# 02_LEDs.net
KiCad netlist of a schematic drawn in Altium Designer
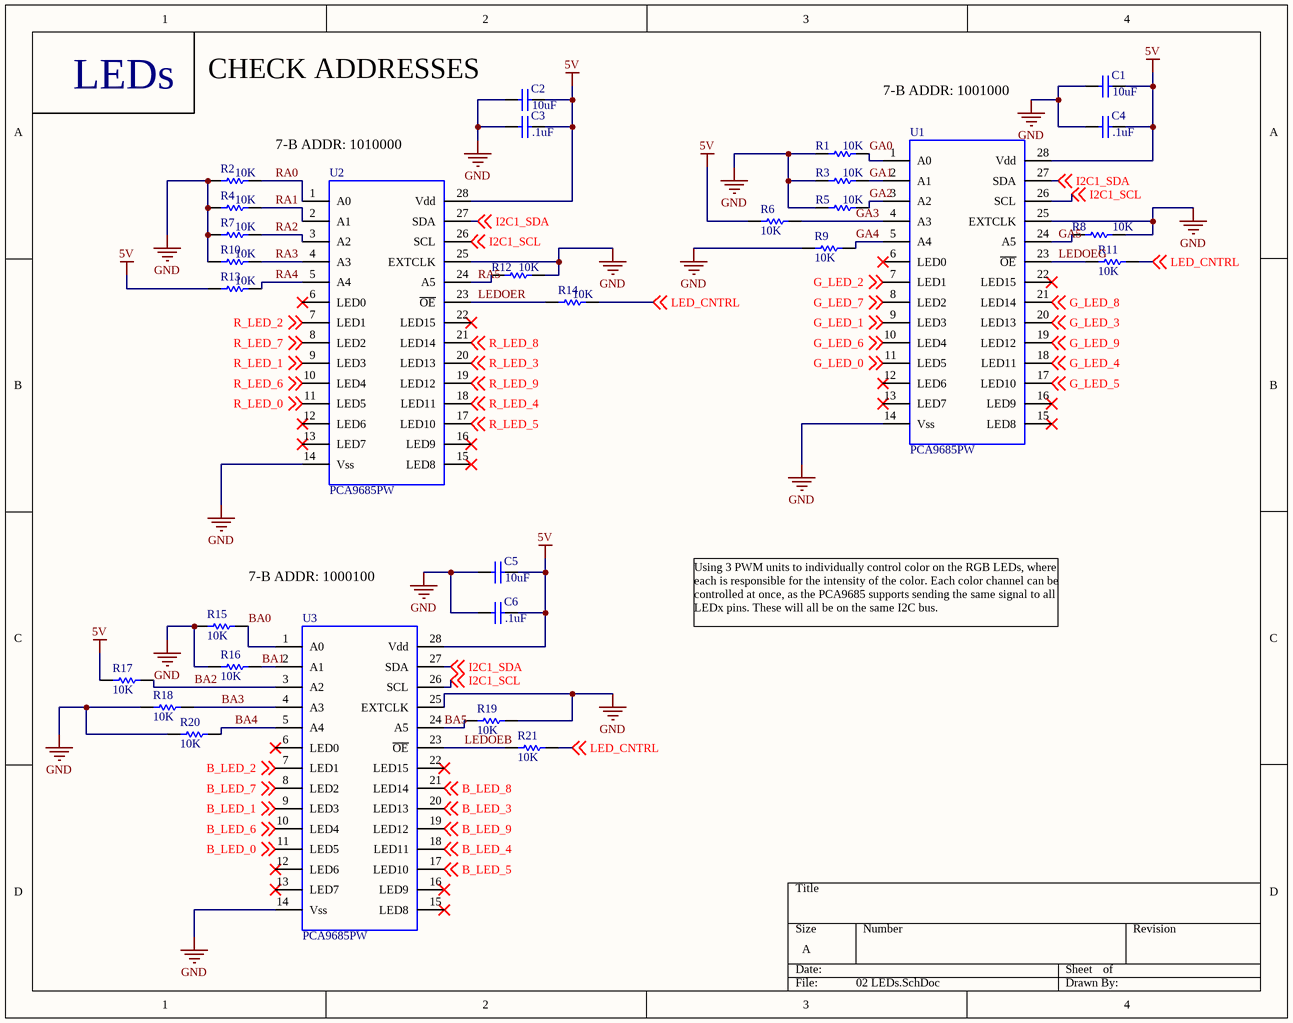
[diagram p0: 02 LEDs.SchDoc]

(export (version "E")
  (design (tool "Eeschema 10.0.6"))
  (components
    (comp (ref "C1")
      (value "10uF")
      (footprint "CAPC2012X135N")
      (description "Cap Ceramic 10uF 16V X5R 10% SMD 0805 85C T/R")
      (fields
        (field (name "MANUFACTURER") "Johanson Dielectrics")
        (field (name "MANUFACTURER PART NUMBER") "160R15X106KV4E")
      )
      (libsource (lib "schlib_truman") (part "CAP_0805_10u_16V"))
    )
    (comp (ref "C2")
      (value "10uF")
      (footprint "CAPC2012X135N")
      (description "Cap Ceramic 10uF 16V X5R 10% SMD 0805 85C T/R")
      (fields
        (field (name "MANUFACTURER") "Johanson Dielectrics")
        (field (name "MANUFACTURER PART NUMBER") "160R15X106KV4E")
      )
      (libsource (lib "schlib_truman") (part "CAP_0805_10u_16V"))
    )
    (comp (ref "C3")
      (value ".1uF")
      (footprint "CAPC2012X135N")
      (description "Cap Ceramic 0.1uF 250V X7T 10% SMD 0805 125C Plastic T/R")
      (fields
        (field (name "MANUFACTURER") "TDK")
        (field (name "MANUFACTURER PART NUMBER") "C2012X7T2E104K125AE")
      )
      (libsource (lib "schlib_truman") (part "CAP_0805_.1u_250V"))
    )
    (comp (ref "C4")
      (value ".1uF")
      (footprint "CAPC2012X135N")
      (description "Cap Ceramic 0.1uF 250V X7T 10% SMD 0805 125C Plastic T/R")
      (fields
        (field (name "MANUFACTURER") "TDK")
        (field (name "MANUFACTURER PART NUMBER") "C2012X7T2E104K125AE")
      )
      (libsource (lib "schlib_truman") (part "CAP_0805_.1u_250V"))
    )
    (comp (ref "C5")
      (value "10uF")
      (footprint "CAPC2012X135N")
      (description "Cap Ceramic 10uF 16V X5R 10% SMD 0805 85C T/R")
      (fields
        (field (name "MANUFACTURER") "Johanson Dielectrics")
        (field (name "MANUFACTURER PART NUMBER") "160R15X106KV4E")
      )
      (libsource (lib "schlib_truman") (part "CAP_0805_10u_16V"))
    )
    (comp (ref "C6")
      (value ".1uF")
      (footprint "CAPC2012X135N")
      (description "Cap Ceramic 0.1uF 250V X7T 10% SMD 0805 125C Plastic T/R")
      (fields
        (field (name "MANUFACTURER") "TDK")
        (field (name "MANUFACTURER PART NUMBER") "C2012X7T2E104K125AE")
      )
      (libsource (lib "schlib_truman") (part "CAP_0805_.1u_250V"))
    )
    (comp (ref "R1")
      (value "RES_0805_10K")
      (footprint "RES0805")
      (description "RES, THICK FILM, 10K, 5%, 0.125W, 0805")
      (fields
        (field (name "MANUFACTURER") "Yageo")
        (field (name "MANUFACTURER PART NUMBER") "RC0805JR-0710KL")
        (field (name "RESISTANCE") "10K")
      )
      (libsource (lib "schlib_truman") (part "RES_0805_10K"))
    )
    (comp (ref "R2")
      (value "RES_0805_10K")
      (footprint "RES0805")
      (description "RES, THICK FILM, 10K, 5%, 0.125W, 0805")
      (fields
        (field (name "MANUFACTURER") "Yageo")
        (field (name "MANUFACTURER PART NUMBER") "RC0805JR-0710KL")
        (field (name "RESISTANCE") "10K")
      )
      (libsource (lib "schlib_truman") (part "RES_0805_10K"))
    )
    (comp (ref "R3")
      (value "RES_0805_10K")
      (footprint "RES0805")
      (description "RES, THICK FILM, 10K, 5%, 0.125W, 0805")
      (fields
        (field (name "MANUFACTURER") "Yageo")
        (field (name "MANUFACTURER PART NUMBER") "RC0805JR-0710KL")
        (field (name "RESISTANCE") "10K")
      )
      (libsource (lib "schlib_truman") (part "RES_0805_10K"))
    )
    (comp (ref "R4")
      (value "RES_0805_10K")
      (footprint "RES0805")
      (description "RES, THICK FILM, 10K, 5%, 0.125W, 0805")
      (fields
        (field (name "MANUFACTURER") "Yageo")
        (field (name "MANUFACTURER PART NUMBER") "RC0805JR-0710KL")
        (field (name "RESISTANCE") "10K")
      )
      (libsource (lib "schlib_truman") (part "RES_0805_10K"))
    )
    (comp (ref "R5")
      (value "RES_0805_10K")
      (footprint "RES0805")
      (description "RES, THICK FILM, 10K, 5%, 0.125W, 0805")
      (fields
        (field (name "MANUFACTURER") "Yageo")
        (field (name "MANUFACTURER PART NUMBER") "RC0805JR-0710KL")
        (field (name "RESISTANCE") "10K")
      )
      (libsource (lib "schlib_truman") (part "RES_0805_10K"))
    )
    (comp (ref "R6")
      (value "RES_0805_10K")
      (footprint "RES0805")
      (description "RES, THICK FILM, 10K, 5%, 0.125W, 0805")
      (fields
        (field (name "MANUFACTURER") "Yageo")
        (field (name "MANUFACTURER PART NUMBER") "RC0805JR-0710KL")
        (field (name "RESISTANCE") "10K")
      )
      (libsource (lib "schlib_truman") (part "RES_0805_10K"))
    )
    (comp (ref "R7")
      (value "RES_0805_10K")
      (footprint "RES0805")
      (description "RES, THICK FILM, 10K, 5%, 0.125W, 0805")
      (fields
        (field (name "MANUFACTURER") "Yageo")
        (field (name "MANUFACTURER PART NUMBER") "RC0805JR-0710KL")
        (field (name "RESISTANCE") "10K")
      )
      (libsource (lib "schlib_truman") (part "RES_0805_10K"))
    )
    (comp (ref "R8")
      (value "RES_0805_10K")
      (footprint "RES0805")
      (description "RES, THICK FILM, 10K, 5%, 0.125W, 0805")
      (fields
        (field (name "MANUFACTURER") "Yageo")
        (field (name "MANUFACTURER PART NUMBER") "RC0805JR-0710KL")
        (field (name "RESISTANCE") "10K")
      )
      (libsource (lib "schlib_truman") (part "RES_0805_10K"))
    )
    (comp (ref "R9")
      (value "RES_0805_10K")
      (footprint "RES0805")
      (description "RES, THICK FILM, 10K, 5%, 0.125W, 0805")
      (fields
        (field (name "MANUFACTURER") "Yageo")
        (field (name "MANUFACTURER PART NUMBER") "RC0805JR-0710KL")
        (field (name "RESISTANCE") "10K")
      )
      (libsource (lib "schlib_truman") (part "RES_0805_10K"))
    )
    (comp (ref "R10")
      (value "RES_0805_10K")
      (footprint "RES0805")
      (description "RES, THICK FILM, 10K, 5%, 0.125W, 0805")
      (fields
        (field (name "MANUFACTURER") "Yageo")
        (field (name "MANUFACTURER PART NUMBER") "RC0805JR-0710KL")
        (field (name "RESISTANCE") "10K")
      )
      (libsource (lib "schlib_truman") (part "RES_0805_10K"))
    )
    (comp (ref "R11")
      (value "RES_0805_10K")
      (footprint "RES0805")
      (description "RES, THICK FILM, 10K, 5%, 0.125W, 0805")
      (fields
        (field (name "MANUFACTURER") "Yageo")
        (field (name "MANUFACTURER PART NUMBER") "RC0805JR-0710KL")
        (field (name "RESISTANCE") "10K")
      )
      (libsource (lib "schlib_truman") (part "RES_0805_10K"))
    )
    (comp (ref "R12")
      (value "RES_0805_10K")
      (footprint "RES0805")
      (description "RES, THICK FILM, 10K, 5%, 0.125W, 0805")
      (fields
        (field (name "MANUFACTURER") "Yageo")
        (field (name "MANUFACTURER PART NUMBER") "RC0805JR-0710KL")
        (field (name "RESISTANCE") "10K")
      )
      (libsource (lib "schlib_truman") (part "RES_0805_10K"))
    )
    (comp (ref "R13")
      (value "RES_0805_10K")
      (footprint "RES0805")
      (description "RES, THICK FILM, 10K, 5%, 0.125W, 0805")
      (fields
        (field (name "MANUFACTURER") "Yageo")
        (field (name "MANUFACTURER PART NUMBER") "RC0805JR-0710KL")
        (field (name "RESISTANCE") "10K")
      )
      (libsource (lib "schlib_truman") (part "RES_0805_10K"))
    )
    (comp (ref "R14")
      (value "RES_0805_10K")
      (footprint "RES0805")
      (description "RES, THICK FILM, 10K, 5%, 0.125W, 0805")
      (fields
        (field (name "MANUFACTURER") "Yageo")
        (field (name "MANUFACTURER PART NUMBER") "RC0805JR-0710KL")
        (field (name "RESISTANCE") "10K")
      )
      (libsource (lib "schlib_truman") (part "RES_0805_10K"))
    )
    (comp (ref "R15")
      (value "RES_0805_10K")
      (footprint "RES0805")
      (description "RES, THICK FILM, 10K, 5%, 0.125W, 0805")
      (fields
        (field (name "MANUFACTURER") "Yageo")
        (field (name "MANUFACTURER PART NUMBER") "RC0805JR-0710KL")
        (field (name "RESISTANCE") "10K")
      )
      (libsource (lib "schlib_truman") (part "RES_0805_10K"))
    )
    (comp (ref "R16")
      (value "RES_0805_10K")
      (footprint "RES0805")
      (description "RES, THICK FILM, 10K, 5%, 0.125W, 0805")
      (fields
        (field (name "MANUFACTURER") "Yageo")
        (field (name "MANUFACTURER PART NUMBER") "RC0805JR-0710KL")
        (field (name "RESISTANCE") "10K")
      )
      (libsource (lib "schlib_truman") (part "RES_0805_10K"))
    )
    (comp (ref "R17")
      (value "RES_0805_10K")
      (footprint "RES0805")
      (description "RES, THICK FILM, 10K, 5%, 0.125W, 0805")
      (fields
        (field (name "MANUFACTURER") "Yageo")
        (field (name "MANUFACTURER PART NUMBER") "RC0805JR-0710KL")
        (field (name "RESISTANCE") "10K")
      )
      (libsource (lib "schlib_truman") (part "RES_0805_10K"))
    )
    (comp (ref "R18")
      (value "RES_0805_10K")
      (footprint "RES0805")
      (description "RES, THICK FILM, 10K, 5%, 0.125W, 0805")
      (fields
        (field (name "MANUFACTURER") "Yageo")
        (field (name "MANUFACTURER PART NUMBER") "RC0805JR-0710KL")
        (field (name "RESISTANCE") "10K")
      )
      (libsource (lib "schlib_truman") (part "RES_0805_10K"))
    )
    (comp (ref "R19")
      (value "RES_0805_10K")
      (footprint "RES0805")
      (description "RES, THICK FILM, 10K, 5%, 0.125W, 0805")
      (fields
        (field (name "MANUFACTURER") "Yageo")
        (field (name "MANUFACTURER PART NUMBER") "RC0805JR-0710KL")
        (field (name "RESISTANCE") "10K")
      )
      (libsource (lib "schlib_truman") (part "RES_0805_10K"))
    )
    (comp (ref "R20")
      (value "RES_0805_10K")
      (footprint "RES0805")
      (description "RES, THICK FILM, 10K, 5%, 0.125W, 0805")
      (fields
        (field (name "MANUFACTURER") "Yageo")
        (field (name "MANUFACTURER PART NUMBER") "RC0805JR-0710KL")
        (field (name "RESISTANCE") "10K")
      )
      (libsource (lib "schlib_truman") (part "RES_0805_10K"))
    )
    (comp (ref "R21")
      (value "RES_0805_10K")
      (footprint "RES0805")
      (description "RES, THICK FILM, 10K, 5%, 0.125W, 0805")
      (fields
        (field (name "MANUFACTURER") "Yageo")
        (field (name "MANUFACTURER PART NUMBER") "RC0805JR-0710KL")
        (field (name "RESISTANCE") "10K")
      )
      (libsource (lib "schlib_truman") (part "RES_0805_10K"))
    )
    (comp (ref "U1")
      (value "PCA9685PW")
      (footprint "TSSOP28")
      (description "IC LED DRIVER RGBA 28-TSSOP")
      (fields
        (field (name "MANUFACTURER") "NXP Semiconductors")
        (field (name "MANUFACTURER PART NUMBER") "PCA9685PW,118")
      )
      (libsource (lib "schlib_truman") (part "PCA9685PW"))
    )
    (comp (ref "U2")
      (value "PCA9685PW")
      (footprint "TSSOP28")
      (description "IC LED DRIVER RGBA 28-TSSOP")
      (fields
        (field (name "MANUFACTURER") "NXP Semiconductors")
        (field (name "MANUFACTURER PART NUMBER") "PCA9685PW,118")
      )
      (libsource (lib "schlib_truman") (part "PCA9685PW"))
    )
    (comp (ref "U3")
      (value "PCA9685PW")
      (footprint "TSSOP28")
      (description "IC LED DRIVER RGBA 28-TSSOP")
      (fields
        (field (name "MANUFACTURER") "NXP Semiconductors")
        (field (name "MANUFACTURER PART NUMBER") "PCA9685PW,118")
      )
      (libsource (lib "schlib_truman") (part "PCA9685PW"))
    )
  )
  (nets
    (net (code "1") (name "/BA0") (class "Default")
      (node (ref "R15") (pin "2") (pinfunction "2_2") (pintype "passive"))
      (node (ref "U3") (pin "1") (pinfunction "A0_1") (pintype "passive"))
    )
    (net (code "2") (name "/BA1") (class "Default")
      (node (ref "R16") (pin "2") (pinfunction "2_2") (pintype "passive"))
      (node (ref "U3") (pin "2") (pinfunction "A1_2") (pintype "passive"))
    )
    (net (code "3") (name "/BA2") (class "Default")
      (node (ref "R17") (pin "2") (pinfunction "2_2") (pintype "passive"))
      (node (ref "U3") (pin "3") (pinfunction "A2_3") (pintype "passive"))
    )
    (net (code "4") (name "/BA3") (class "Default")
      (node (ref "R18") (pin "2") (pinfunction "2_2") (pintype "passive"))
      (node (ref "U3") (pin "4") (pinfunction "A3_4") (pintype "passive"))
    )
    (net (code "5") (name "/BA4") (class "Default")
      (node (ref "R20") (pin "2") (pinfunction "2_2") (pintype "passive"))
      (node (ref "U3") (pin "5") (pinfunction "A4_5") (pintype "passive"))
    )
    (net (code "6") (name "/BA5") (class "Default")
      (node (ref "R19") (pin "1") (pinfunction "1_1") (pintype "passive"))
      (node (ref "U3") (pin "24") (pinfunction "A5_24") (pintype "passive"))
    )
    (net (code "7") (name "/GA0") (class "Default")
      (node (ref "R1") (pin "2") (pinfunction "2_2") (pintype "passive"))
      (node (ref "U1") (pin "1") (pinfunction "A0_1") (pintype "passive"))
    )
    (net (code "8") (name "/GA1") (class "Default")
      (node (ref "R3") (pin "2") (pinfunction "2_2") (pintype "passive"))
      (node (ref "U1") (pin "2") (pinfunction "A1_2") (pintype "passive"))
    )
    (net (code "9") (name "/GA2") (class "Default")
      (node (ref "R5") (pin "2") (pinfunction "2_2") (pintype "passive"))
      (node (ref "U1") (pin "3") (pinfunction "A2_3") (pintype "passive"))
    )
    (net (code "10") (name "/GA3") (class "Default")
      (node (ref "R6") (pin "2") (pinfunction "2_2") (pintype "passive"))
      (node (ref "U1") (pin "4") (pinfunction "A3_4") (pintype "passive"))
    )
    (net (code "11") (name "/GA4") (class "Default")
      (node (ref "R9") (pin "2") (pinfunction "2_2") (pintype "passive"))
      (node (ref "U1") (pin "5") (pinfunction "A4_5") (pintype "passive"))
    )
    (net (code "12") (name "/GA5") (class "Default")
      (node (ref "R8") (pin "1") (pinfunction "1_1") (pintype "passive"))
      (node (ref "U1") (pin "24") (pinfunction "A5_24") (pintype "passive"))
    )
    (net (code "13") (name "/LEDOEB") (class "Default")
      (node (ref "R21") (pin "1") (pinfunction "1_1") (pintype "passive"))
      (node (ref "U3") (pin "23") (pinfunction "~{OE}_23") (pintype "passive"))
    )
    (net (code "14") (name "/LEDOEG") (class "Default")
      (node (ref "R11") (pin "1") (pinfunction "1_1") (pintype "passive"))
      (node (ref "U1") (pin "23") (pinfunction "~{OE}_23") (pintype "passive"))
    )
    (net (code "15") (name "/LEDOER") (class "Default")
      (node (ref "R14") (pin "1") (pinfunction "1_1") (pintype "passive"))
      (node (ref "U2") (pin "23") (pinfunction "~{OE}_23") (pintype "passive"))
    )
    (net (code "16") (name "/RA0") (class "Default")
      (node (ref "R2") (pin "2") (pinfunction "2_2") (pintype "passive"))
      (node (ref "U2") (pin "1") (pinfunction "A0_1") (pintype "passive"))
    )
    (net (code "17") (name "/RA1") (class "Default")
      (node (ref "R4") (pin "2") (pinfunction "2_2") (pintype "passive"))
      (node (ref "U2") (pin "2") (pinfunction "A1_2") (pintype "passive"))
    )
    (net (code "18") (name "/RA2") (class "Default")
      (node (ref "R7") (pin "2") (pinfunction "2_2") (pintype "passive"))
      (node (ref "U2") (pin "3") (pinfunction "A2_3") (pintype "passive"))
    )
    (net (code "19") (name "/RA3") (class "Default")
      (node (ref "R10") (pin "2") (pinfunction "2_2") (pintype "passive"))
      (node (ref "U2") (pin "4") (pinfunction "A3_4") (pintype "passive"))
    )
    (net (code "20") (name "/RA4") (class "Default")
      (node (ref "R13") (pin "2") (pinfunction "2_2") (pintype "passive"))
      (node (ref "U2") (pin "5") (pinfunction "A4_5") (pintype "passive"))
    )
    (net (code "21") (name "/RA5") (class "Default")
      (node (ref "R12") (pin "1") (pinfunction "1_1") (pintype "passive"))
      (node (ref "U2") (pin "24") (pinfunction "A5_24") (pintype "passive"))
    )
    (net (code "22") (name "5V") (class "Default")
      (node (ref "C1") (pin "2") (pinfunction "2_2") (pintype "passive"))
      (node (ref "C2") (pin "2") (pinfunction "2_2") (pintype "passive"))
      (node (ref "C3") (pin "2") (pinfunction "2_2") (pintype "passive"))
      (node (ref "C4") (pin "2") (pinfunction "2_2") (pintype "passive"))
      (node (ref "C5") (pin "2") (pinfunction "2_2") (pintype "passive"))
      (node (ref "C6") (pin "2") (pinfunction "2_2") (pintype "passive"))
      (node (ref "R13") (pin "1") (pinfunction "1_1") (pintype "passive"))
      (node (ref "R17") (pin "1") (pinfunction "1_1") (pintype "passive"))
      (node (ref "R6") (pin "1") (pinfunction "1_1") (pintype "passive"))
      (node (ref "U1") (pin "28") (pinfunction "Vdd_28") (pintype "passive"))
      (node (ref "U2") (pin "28") (pinfunction "Vdd_28") (pintype "passive"))
      (node (ref "U3") (pin "28") (pinfunction "Vdd_28") (pintype "passive"))
    )
    (net (code "23") (name "B_LED_0") (class "Default")
      (node (ref "U3") (pin "11") (pinfunction "LED5_11") (pintype "passive"))
    )
    (net (code "24") (name "B_LED_1") (class "Default")
      (node (ref "U3") (pin "9") (pinfunction "LED3_9") (pintype "passive"))
    )
    (net (code "25") (name "B_LED_2") (class "Default")
      (node (ref "U3") (pin "7") (pinfunction "LED1_7") (pintype "passive"))
    )
    (net (code "26") (name "B_LED_3") (class "Default")
      (node (ref "U3") (pin "20") (pinfunction "LED13_20") (pintype "passive"))
    )
    (net (code "27") (name "B_LED_4") (class "Default")
      (node (ref "U3") (pin "18") (pinfunction "LED11_18") (pintype "passive"))
    )
    (net (code "28") (name "B_LED_5") (class "Default")
      (node (ref "U3") (pin "17") (pinfunction "LED10_17") (pintype "passive"))
    )
    (net (code "29") (name "B_LED_6") (class "Default")
      (node (ref "U3") (pin "10") (pinfunction "LED4_10") (pintype "passive"))
    )
    (net (code "30") (name "B_LED_7") (class "Default")
      (node (ref "U3") (pin "8") (pinfunction "LED2_8") (pintype "passive"))
    )
    (net (code "31") (name "B_LED_8") (class "Default")
      (node (ref "U3") (pin "21") (pinfunction "LED14_21") (pintype "passive"))
    )
    (net (code "32") (name "B_LED_9") (class "Default")
      (node (ref "U3") (pin "19") (pinfunction "LED12_19") (pintype "passive"))
    )
    (net (code "33") (name "GND") (class "Default")
      (node (ref "C1") (pin "1") (pinfunction "1_1") (pintype "passive"))
      (node (ref "C2") (pin "1") (pinfunction "1_1") (pintype "passive"))
      (node (ref "C3") (pin "1") (pinfunction "1_1") (pintype "passive"))
      (node (ref "C4") (pin "1") (pinfunction "1_1") (pintype "passive"))
      (node (ref "C5") (pin "1") (pinfunction "1_1") (pintype "passive"))
      (node (ref "C6") (pin "1") (pinfunction "1_1") (pintype "passive"))
      (node (ref "R1") (pin "1") (pinfunction "1_1") (pintype "passive"))
      (node (ref "R10") (pin "1") (pinfunction "1_1") (pintype "passive"))
      (node (ref "R12") (pin "2") (pinfunction "2_2") (pintype "passive"))
      (node (ref "R15") (pin "1") (pinfunction "1_1") (pintype "passive"))
      (node (ref "R16") (pin "1") (pinfunction "1_1") (pintype "passive"))
      (node (ref "R18") (pin "1") (pinfunction "1_1") (pintype "passive"))
      (node (ref "R19") (pin "2") (pinfunction "2_2") (pintype "passive"))
      (node (ref "R2") (pin "1") (pinfunction "1_1") (pintype "passive"))
      (node (ref "R20") (pin "1") (pinfunction "1_1") (pintype "passive"))
      (node (ref "R3") (pin "1") (pinfunction "1_1") (pintype "passive"))
      (node (ref "R4") (pin "1") (pinfunction "1_1") (pintype "passive"))
      (node (ref "R5") (pin "1") (pinfunction "1_1") (pintype "passive"))
      (node (ref "R7") (pin "1") (pinfunction "1_1") (pintype "passive"))
      (node (ref "R8") (pin "2") (pinfunction "2_2") (pintype "passive"))
      (node (ref "R9") (pin "1") (pinfunction "1_1") (pintype "passive"))
      (node (ref "U1") (pin "14") (pinfunction "Vss_14") (pintype "passive"))
      (node (ref "U1") (pin "25") (pinfunction "EXTCLK_25") (pintype "passive"))
      (node (ref "U2") (pin "14") (pinfunction "Vss_14") (pintype "passive"))
      (node (ref "U2") (pin "25") (pinfunction "EXTCLK_25") (pintype "passive"))
      (node (ref "U3") (pin "14") (pinfunction "Vss_14") (pintype "passive"))
      (node (ref "U3") (pin "25") (pinfunction "EXTCLK_25") (pintype "passive"))
    )
    (net (code "34") (name "G_LED_0") (class "Default")
      (node (ref "U1") (pin "11") (pinfunction "LED5_11") (pintype "passive"))
    )
    (net (code "35") (name "G_LED_1") (class "Default")
      (node (ref "U1") (pin "9") (pinfunction "LED3_9") (pintype "passive"))
    )
    (net (code "36") (name "G_LED_2") (class "Default")
      (node (ref "U1") (pin "7") (pinfunction "LED1_7") (pintype "passive"))
    )
    (net (code "37") (name "G_LED_3") (class "Default")
      (node (ref "U1") (pin "20") (pinfunction "LED13_20") (pintype "passive"))
    )
    (net (code "38") (name "G_LED_4") (class "Default")
      (node (ref "U1") (pin "18") (pinfunction "LED11_18") (pintype "passive"))
    )
    (net (code "39") (name "G_LED_5") (class "Default")
      (node (ref "U1") (pin "17") (pinfunction "LED10_17") (pintype "passive"))
    )
    (net (code "40") (name "G_LED_6") (class "Default")
      (node (ref "U1") (pin "10") (pinfunction "LED4_10") (pintype "passive"))
    )
    (net (code "41") (name "G_LED_7") (class "Default")
      (node (ref "U1") (pin "8") (pinfunction "LED2_8") (pintype "passive"))
    )
    (net (code "42") (name "G_LED_8") (class "Default")
      (node (ref "U1") (pin "21") (pinfunction "LED14_21") (pintype "passive"))
    )
    (net (code "43") (name "G_LED_9") (class "Default")
      (node (ref "U1") (pin "19") (pinfunction "LED12_19") (pintype "passive"))
    )
    (net (code "44") (name "I2C1_SCL") (class "Default")
      (node (ref "U1") (pin "26") (pinfunction "SCL_26") (pintype "passive"))
      (node (ref "U2") (pin "26") (pinfunction "SCL_26") (pintype "passive"))
      (node (ref "U3") (pin "26") (pinfunction "SCL_26") (pintype "passive"))
    )
    (net (code "45") (name "I2C1_SDA") (class "Default")
      (node (ref "U1") (pin "27") (pinfunction "SDA_27") (pintype "passive"))
      (node (ref "U2") (pin "27") (pinfunction "SDA_27") (pintype "passive"))
      (node (ref "U3") (pin "27") (pinfunction "SDA_27") (pintype "passive"))
    )
    (net (code "46") (name "LED_CNTRL") (class "Default")
      (node (ref "R11") (pin "2") (pinfunction "2_2") (pintype "passive"))
      (node (ref "R14") (pin "2") (pinfunction "2_2") (pintype "passive"))
      (node (ref "R21") (pin "2") (pinfunction "2_2") (pintype "passive"))
    )
    (net (code "47") (name "R_LED_0") (class "Default")
      (node (ref "U2") (pin "11") (pinfunction "LED5_11") (pintype "passive"))
    )
    (net (code "48") (name "R_LED_1") (class "Default")
      (node (ref "U2") (pin "9") (pinfunction "LED3_9") (pintype "passive"))
    )
    (net (code "49") (name "R_LED_2") (class "Default")
      (node (ref "U2") (pin "7") (pinfunction "LED1_7") (pintype "passive"))
    )
    (net (code "50") (name "R_LED_3") (class "Default")
      (node (ref "U2") (pin "20") (pinfunction "LED13_20") (pintype "passive"))
    )
    (net (code "51") (name "R_LED_4") (class "Default")
      (node (ref "U2") (pin "18") (pinfunction "LED11_18") (pintype "passive"))
    )
    (net (code "52") (name "R_LED_5") (class "Default")
      (node (ref "U2") (pin "17") (pinfunction "LED10_17") (pintype "passive"))
    )
    (net (code "53") (name "R_LED_6") (class "Default")
      (node (ref "U2") (pin "10") (pinfunction "LED4_10") (pintype "passive"))
    )
    (net (code "54") (name "R_LED_7") (class "Default")
      (node (ref "U2") (pin "8") (pinfunction "LED2_8") (pintype "passive"))
    )
    (net (code "55") (name "R_LED_8") (class "Default")
      (node (ref "U2") (pin "21") (pinfunction "LED14_21") (pintype "passive"))
    )
    (net (code "56") (name "R_LED_9") (class "Default")
      (node (ref "U2") (pin "19") (pinfunction "LED12_19") (pintype "passive"))
    )
    (net (code "57") (name "unconnected-(U1-LED0-Pad6)") (class "Default")
      (node (ref "U1") (pin "6") (pinfunction "LED0_6") (pintype "passive+no_connect"))
    )
    (net (code "58") (name "unconnected-(U1-LED6-Pad12)") (class "Default")
      (node (ref "U1") (pin "12") (pinfunction "LED6_12") (pintype "passive+no_connect"))
    )
    (net (code "59") (name "unconnected-(U1-LED7-Pad13)") (class "Default")
      (node (ref "U1") (pin "13") (pinfunction "LED7_13") (pintype "passive+no_connect"))
    )
    (net (code "60") (name "unconnected-(U1-LED8-Pad15)") (class "Default")
      (node (ref "U1") (pin "15") (pinfunction "LED8_15") (pintype "passive+no_connect"))
    )
    (net (code "61") (name "unconnected-(U1-LED9-Pad16)") (class "Default")
      (node (ref "U1") (pin "16") (pinfunction "LED9_16") (pintype "passive+no_connect"))
    )
    (net (code "62") (name "unconnected-(U1-LED15-Pad22)") (class "Default")
      (node (ref "U1") (pin "22") (pinfunction "LED15_22") (pintype "passive+no_connect"))
    )
    (net (code "63") (name "unconnected-(U2-LED0-Pad6)") (class "Default")
      (node (ref "U2") (pin "6") (pinfunction "LED0_6") (pintype "passive+no_connect"))
    )
    (net (code "64") (name "unconnected-(U2-LED6-Pad12)") (class "Default")
      (node (ref "U2") (pin "12") (pinfunction "LED6_12") (pintype "passive+no_connect"))
    )
    (net (code "65") (name "unconnected-(U2-LED7-Pad13)") (class "Default")
      (node (ref "U2") (pin "13") (pinfunction "LED7_13") (pintype "passive+no_connect"))
    )
    (net (code "66") (name "unconnected-(U2-LED8-Pad15)") (class "Default")
      (node (ref "U2") (pin "15") (pinfunction "LED8_15") (pintype "passive+no_connect"))
    )
    (net (code "67") (name "unconnected-(U2-LED9-Pad16)") (class "Default")
      (node (ref "U2") (pin "16") (pinfunction "LED9_16") (pintype "passive+no_connect"))
    )
    (net (code "68") (name "unconnected-(U2-LED15-Pad22)") (class "Default")
      (node (ref "U2") (pin "22") (pinfunction "LED15_22") (pintype "passive+no_connect"))
    )
    (net (code "69") (name "unconnected-(U3-LED0-Pad6)") (class "Default")
      (node (ref "U3") (pin "6") (pinfunction "LED0_6") (pintype "passive+no_connect"))
    )
    (net (code "70") (name "unconnected-(U3-LED6-Pad12)") (class "Default")
      (node (ref "U3") (pin "12") (pinfunction "LED6_12") (pintype "passive+no_connect"))
    )
    (net (code "71") (name "unconnected-(U3-LED7-Pad13)") (class "Default")
      (node (ref "U3") (pin "13") (pinfunction "LED7_13") (pintype "passive+no_connect"))
    )
    (net (code "72") (name "unconnected-(U3-LED8-Pad15)") (class "Default")
      (node (ref "U3") (pin "15") (pinfunction "LED8_15") (pintype "passive+no_connect"))
    )
    (net (code "73") (name "unconnected-(U3-LED9-Pad16)") (class "Default")
      (node (ref "U3") (pin "16") (pinfunction "LED9_16") (pintype "passive+no_connect"))
    )
    (net (code "74") (name "unconnected-(U3-LED15-Pad22)") (class "Default")
      (node (ref "U3") (pin "22") (pinfunction "LED15_22") (pintype "passive+no_connect"))
    )
  )
)
